# merkur-23m10.net
KiCad netlist of a schematic drawn in EAGLE
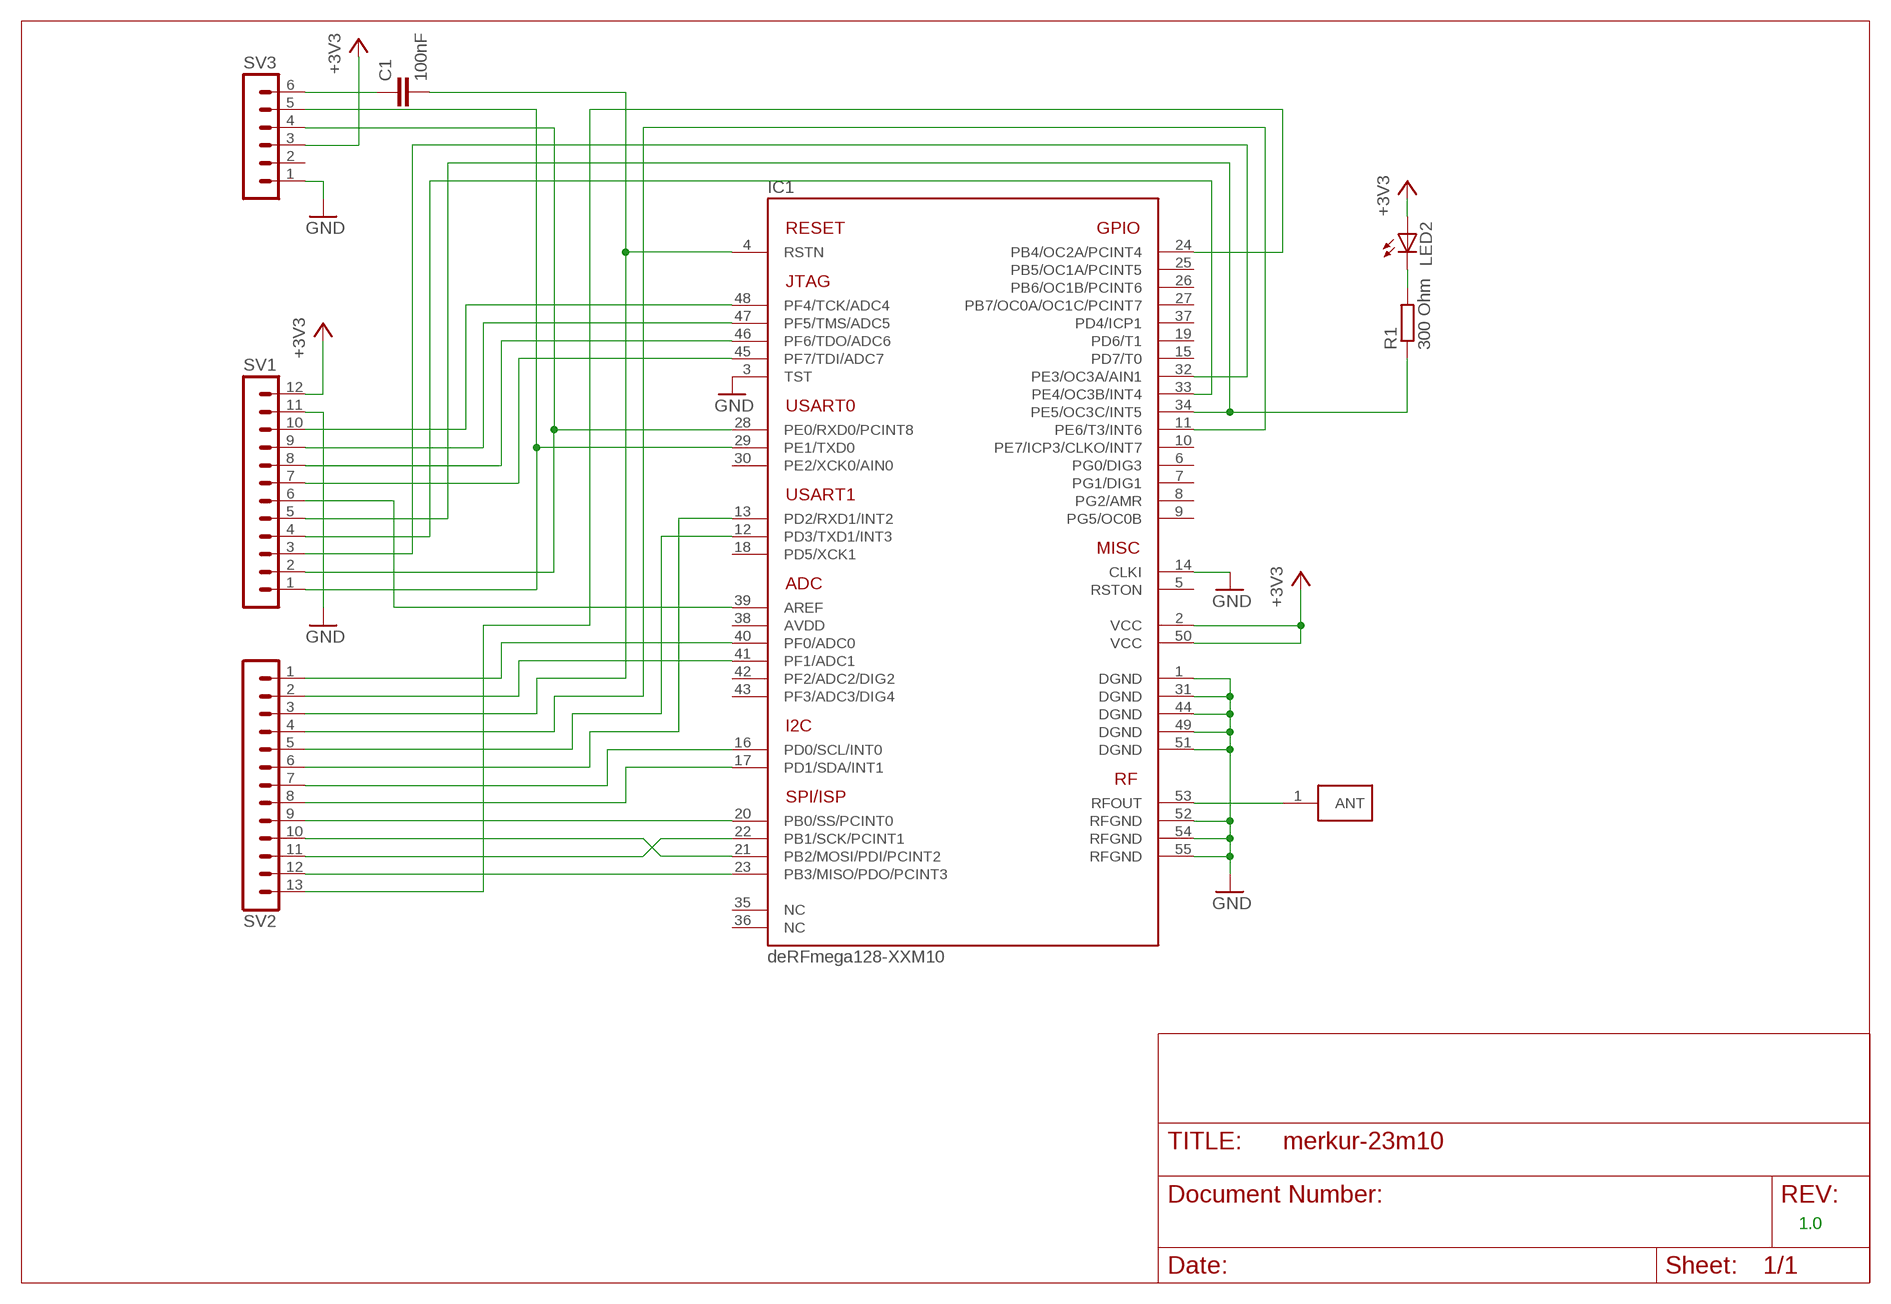
[diagram p0: schematic, sheet 1]

(export (version "E")
  (design (tool "Eeschema 10.0.6"))
  (components
    (comp (ref "C1")
      (value "100nF")
      (footprint "eagle-import:C0603")
      (libsource (lib "eagle-import") (part "C-EUC0603"))
    )
    (comp (ref "IC1")
      (value "DERFMEGA128-XXM10")
      (footprint "eagle-import:A-M10")
      (libsource (lib "eagle-import") (part "DERFMEGA128-XXM10"))
    )
    (comp (ref "LED2")
      (value "LEDCHIP-LED0603")
      (footprint "eagle-import:CHIP-LED0603")
      (libsource (lib "eagle-import") (part "LEDCHIP-LED0603"))
    )
    (comp (ref "R1")
      (value "300 Ohm")
      (footprint "eagle-import:R0603")
      (libsource (lib "eagle-import") (part "R-EU_R0603"))
    )
    (comp (ref "SV1")
      (value "MA12-1")
      (footprint "eagle-import:MA12-1")
      (libsource (lib "eagle-import") (part "MA12-1"))
    )
    (comp (ref "SV2")
      (value "MA13-1")
      (footprint "eagle-import:MA13-1")
      (libsource (lib "eagle-import") (part "MA13-1"))
    )
    (comp (ref "SV3")
      (value "MA06-1")
      (footprint "eagle-import:MA06-1")
      (libsource (lib "eagle-import") (part "MA06-1"))
    )
    (comp (ref "U$1")
      (value "PAD")
      (footprint "eagle-import:FE05-1")
      (libsource (lib "eagle-import") (part "PAD"))
    )
  )
  (nets
    (net (code "1") (name "+3V3") (class "Default")
      (node (ref "IC1") (pin "2") (pinfunction "VCC_2") (pintype "power_in"))
      (node (ref "IC1") (pin "50") (pinfunction "VCC_50") (pintype "power_in"))
      (node (ref "LED2") (pin "A") (pinfunction "A_A") (pintype "passive"))
      (node (ref "SV1") (pin "12") (pinfunction "12_12") (pintype "passive"))
      (node (ref "SV3") (pin "3") (pinfunction "3_3") (pintype "passive"))
    )
    (net (code "2") (name "/AVDD") (class "Default")
      (node (ref "IC1") (pin "38") (pinfunction "AVDD_38") (pintype "power_in"))
    )
    (net (code "3") (name "GND") (class "Default")
      (node (ref "IC1") (pin "1") (pinfunction "DGND_1") (pintype "power_in"))
      (node (ref "IC1") (pin "14") (pinfunction "CLKI_14") (pintype "input"))
      (node (ref "IC1") (pin "3") (pinfunction "TST_3") (pintype "bidirectional"))
      (node (ref "IC1") (pin "31") (pinfunction "DGND_31") (pintype "power_in"))
      (node (ref "IC1") (pin "44") (pinfunction "DGND_44") (pintype "power_in"))
      (node (ref "IC1") (pin "49") (pinfunction "DGND_49") (pintype "power_in"))
      (node (ref "IC1") (pin "51") (pinfunction "DGND_51") (pintype "power_in"))
      (node (ref "IC1") (pin "52") (pinfunction "RFGND_52") (pintype "power_in"))
      (node (ref "IC1") (pin "54") (pinfunction "RFGND_54") (pintype "power_in"))
      (node (ref "IC1") (pin "55") (pinfunction "RFGND_55") (pintype "power_in"))
      (node (ref "SV1") (pin "11") (pinfunction "11_11") (pintype "passive"))
      (node (ref "SV3") (pin "1") (pinfunction "1_1") (pintype "passive"))
    )
    (net (code "4") (name "Net-(C1-Pad1)") (class "Default")
      (node (ref "C1") (pin "1") (pinfunction "1_1") (pintype "passive"))
      (node (ref "SV3") (pin "6") (pinfunction "6_6") (pintype "passive"))
    )
    (net (code "5") (name "Net-(IC1-AREF)") (class "Default")
      (node (ref "IC1") (pin "39") (pinfunction "AREF_39") (pintype "bidirectional"))
      (node (ref "SV1") (pin "6") (pinfunction "6_6") (pintype "passive"))
    )
    (net (code "6") (name "Net-(IC1-PB0{slash}SS{slash}PCINT0)") (class "Default")
      (node (ref "IC1") (pin "20") (pinfunction "PB0/SS/PCINT0_20") (pintype "bidirectional"))
      (node (ref "SV2") (pin "9") (pinfunction "9_9") (pintype "passive"))
    )
    (net (code "7") (name "Net-(IC1-PB1{slash}SCK{slash}PCINT1)") (class "Default")
      (node (ref "IC1") (pin "22") (pinfunction "PB1/SCK/PCINT1_22") (pintype "bidirectional"))
      (node (ref "SV2") (pin "11") (pinfunction "11_11") (pintype "passive"))
    )
    (net (code "8") (name "Net-(IC1-PB2{slash}MOSI{slash}PDI{slash}PCINT2)") (class "Default")
      (node (ref "IC1") (pin "21") (pinfunction "PB2/MOSI/PDI/PCINT2_21") (pintype "bidirectional"))
      (node (ref "SV2") (pin "10") (pinfunction "10_10") (pintype "passive"))
    )
    (net (code "9") (name "Net-(IC1-PB3{slash}MISO{slash}PDO{slash}PCINT3)") (class "Default")
      (node (ref "IC1") (pin "23") (pinfunction "PB3/MISO/PDO/PCINT3_23") (pintype "bidirectional"))
      (node (ref "SV2") (pin "12") (pinfunction "12_12") (pintype "passive"))
    )
    (net (code "10") (name "Net-(IC1-PB4{slash}OC2A{slash}PCINT4)") (class "Default")
      (node (ref "IC1") (pin "24") (pinfunction "PB4/OC2A/PCINT4_24") (pintype "bidirectional"))
      (node (ref "SV2") (pin "13") (pinfunction "13_13") (pintype "passive"))
    )
    (net (code "11") (name "Net-(IC1-PD0{slash}SCL{slash}INT0)") (class "Default")
      (node (ref "IC1") (pin "16") (pinfunction "PD0/SCL/INT0_16") (pintype "bidirectional"))
      (node (ref "SV2") (pin "7") (pinfunction "7_7") (pintype "passive"))
    )
    (net (code "12") (name "Net-(IC1-PD1{slash}SDA{slash}INT1)") (class "Default")
      (node (ref "IC1") (pin "17") (pinfunction "PD1/SDA/INT1_17") (pintype "bidirectional"))
      (node (ref "SV2") (pin "8") (pinfunction "8_8") (pintype "passive"))
    )
    (net (code "13") (name "Net-(IC1-PD2{slash}RXD1{slash}INT2)") (class "Default")
      (node (ref "IC1") (pin "13") (pinfunction "PD2/RXD1/INT2_13") (pintype "bidirectional"))
      (node (ref "SV2") (pin "6") (pinfunction "6_6") (pintype "passive"))
    )
    (net (code "14") (name "Net-(IC1-PD3{slash}TXD1{slash}INT3)") (class "Default")
      (node (ref "IC1") (pin "12") (pinfunction "PD3/TXD1/INT3_12") (pintype "bidirectional"))
      (node (ref "SV2") (pin "5") (pinfunction "5_5") (pintype "passive"))
    )
    (net (code "15") (name "Net-(IC1-PE0{slash}RXD0{slash}PCINT8)") (class "Default")
      (node (ref "IC1") (pin "28") (pinfunction "PE0/RXD0/PCINT8_28") (pintype "bidirectional"))
      (node (ref "SV1") (pin "2") (pinfunction "2_2") (pintype "passive"))
      (node (ref "SV3") (pin "4") (pinfunction "4_4") (pintype "passive"))
    )
    (net (code "16") (name "Net-(IC1-PE1{slash}TXD0)") (class "Default")
      (node (ref "IC1") (pin "29") (pinfunction "PE1/TXD0_29") (pintype "bidirectional"))
      (node (ref "SV1") (pin "1") (pinfunction "1_1") (pintype "passive"))
      (node (ref "SV3") (pin "5") (pinfunction "5_5") (pintype "passive"))
    )
    (net (code "17") (name "Net-(IC1-PE3{slash}OC3A{slash}AIN1)") (class "Default")
      (node (ref "IC1") (pin "32") (pinfunction "PE3/OC3A/AIN1_32") (pintype "bidirectional"))
      (node (ref "SV1") (pin "3") (pinfunction "3_3") (pintype "passive"))
    )
    (net (code "18") (name "Net-(IC1-PE4{slash}OC3B{slash}INT4)") (class "Default")
      (node (ref "IC1") (pin "33") (pinfunction "PE4/OC3B/INT4_33") (pintype "bidirectional"))
      (node (ref "SV1") (pin "4") (pinfunction "4_4") (pintype "passive"))
    )
    (net (code "19") (name "Net-(IC1-PE5{slash}OC3C{slash}INT5)") (class "Default")
      (node (ref "IC1") (pin "34") (pinfunction "PE5/OC3C/INT5_34") (pintype "bidirectional"))
      (node (ref "R1") (pin "1") (pinfunction "1_1") (pintype "passive"))
      (node (ref "SV1") (pin "5") (pinfunction "5_5") (pintype "passive"))
    )
    (net (code "20") (name "Net-(IC1-PE6{slash}T3{slash}INT6)") (class "Default")
      (node (ref "IC1") (pin "11") (pinfunction "PE6/T3/INT6_11") (pintype "bidirectional"))
      (node (ref "SV2") (pin "4") (pinfunction "4_4") (pintype "passive"))
    )
    (net (code "21") (name "Net-(IC1-PF0{slash}ADC0)") (class "Default")
      (node (ref "IC1") (pin "40") (pinfunction "PF0/ADC0_40") (pintype "bidirectional"))
      (node (ref "SV2") (pin "1") (pinfunction "1_1") (pintype "passive"))
    )
    (net (code "22") (name "Net-(IC1-PF1{slash}ADC1)") (class "Default")
      (node (ref "IC1") (pin "41") (pinfunction "PF1/ADC1_41") (pintype "bidirectional"))
      (node (ref "SV2") (pin "2") (pinfunction "2_2") (pintype "passive"))
    )
    (net (code "23") (name "Net-(IC1-PF4{slash}TCK{slash}ADC4)") (class "Default")
      (node (ref "IC1") (pin "48") (pinfunction "PF4/TCK/ADC4_48") (pintype "bidirectional"))
      (node (ref "SV1") (pin "10") (pinfunction "10_10") (pintype "passive"))
    )
    (net (code "24") (name "Net-(IC1-PF5{slash}TMS{slash}ADC5)") (class "Default")
      (node (ref "IC1") (pin "47") (pinfunction "PF5/TMS/ADC5_47") (pintype "bidirectional"))
      (node (ref "SV1") (pin "9") (pinfunction "9_9") (pintype "passive"))
    )
    (net (code "25") (name "Net-(IC1-PF6{slash}TDO{slash}ADC6)") (class "Default")
      (node (ref "IC1") (pin "46") (pinfunction "PF6/TDO/ADC6_46") (pintype "bidirectional"))
      (node (ref "SV1") (pin "8") (pinfunction "8_8") (pintype "passive"))
    )
    (net (code "26") (name "Net-(IC1-PF7{slash}TDI{slash}ADC7)") (class "Default")
      (node (ref "IC1") (pin "45") (pinfunction "PF7/TDI/ADC7_45") (pintype "bidirectional"))
      (node (ref "SV1") (pin "7") (pinfunction "7_7") (pintype "passive"))
    )
    (net (code "27") (name "Net-(IC1-RFOUT)") (class "Default")
      (node (ref "IC1") (pin "53") (pinfunction "RFOUT_53") (pintype "power_in"))
      (node (ref "U$1") (pin "1") (pinfunction "ANT_1") (pintype "output"))
    )
    (net (code "28") (name "Net-(IC1-RSTN)") (class "Default")
      (node (ref "C1") (pin "2") (pinfunction "2_2") (pintype "passive"))
      (node (ref "IC1") (pin "4") (pinfunction "RSTN_4") (pintype "input"))
      (node (ref "SV2") (pin "3") (pinfunction "3_3") (pintype "passive"))
    )
    (net (code "29") (name "Net-(LED2-PadC)") (class "Default")
      (node (ref "LED2") (pin "C") (pinfunction "C_C") (pintype "passive"))
      (node (ref "R1") (pin "2") (pinfunction "2_2") (pintype "passive"))
    )
    (net (code "30") (name "unconnected-(IC1-NC-Pad35)") (class "Default")
      (node (ref "IC1") (pin "35") (pinfunction "NC_35") (pintype "no_connect"))
    )
    (net (code "31") (name "unconnected-(IC1-NC-Pad36)") (class "Default")
      (node (ref "IC1") (pin "36") (pinfunction "NC_36") (pintype "no_connect"))
    )
    (net (code "32") (name "unconnected-(IC1-PB5{slash}OC1A{slash}PCINT5-Pad25)") (class "Default")
      (node (ref "IC1") (pin "25") (pinfunction "PB5/OC1A/PCINT5_25") (pintype "bidirectional"))
    )
    (net (code "33") (name "unconnected-(IC1-PB6{slash}OC1B{slash}PCINT6-Pad26)") (class "Default")
      (node (ref "IC1") (pin "26") (pinfunction "PB6/OC1B/PCINT6_26") (pintype "bidirectional"))
    )
    (net (code "34") (name "unconnected-(IC1-PB7{slash}OC0A{slash}OC1C{slash}PCINT7-Pad27)") (class "Default")
      (node (ref "IC1") (pin "27") (pinfunction "PB7/OC0A/OC1C/PCINT7_27") (pintype "bidirectional"))
    )
    (net (code "35") (name "unconnected-(IC1-PD4{slash}ICP1-Pad37)") (class "Default")
      (node (ref "IC1") (pin "37") (pinfunction "PD4/ICP1_37") (pintype "bidirectional"))
    )
    (net (code "36") (name "unconnected-(IC1-PD5{slash}XCK1-Pad18)") (class "Default")
      (node (ref "IC1") (pin "18") (pinfunction "PD5/XCK1_18") (pintype "bidirectional"))
    )
    (net (code "37") (name "unconnected-(IC1-PD6{slash}T1-Pad19)") (class "Default")
      (node (ref "IC1") (pin "19") (pinfunction "PD6/T1_19") (pintype "bidirectional"))
    )
    (net (code "38") (name "unconnected-(IC1-PD7{slash}T0-Pad15)") (class "Default")
      (node (ref "IC1") (pin "15") (pinfunction "PD7/T0_15") (pintype "bidirectional"))
    )
    (net (code "39") (name "unconnected-(IC1-PE2{slash}XCK0{slash}AIN0-Pad30)") (class "Default")
      (node (ref "IC1") (pin "30") (pinfunction "PE2/XCK0/AIN0_30") (pintype "bidirectional"))
    )
    (net (code "40") (name "unconnected-(IC1-PE7{slash}ICP3{slash}CLKO{slash}INT7-Pad10)") (class "Default")
      (node (ref "IC1") (pin "10") (pinfunction "PE7/ICP3/CLKO/INT7_10") (pintype "bidirectional"))
    )
    (net (code "41") (name "unconnected-(IC1-PF2{slash}ADC2{slash}DIG2-Pad42)") (class "Default")
      (node (ref "IC1") (pin "42") (pinfunction "PF2/ADC2/DIG2_42") (pintype "bidirectional"))
    )
    (net (code "42") (name "unconnected-(IC1-PF3{slash}ADC3{slash}DIG4-Pad43)") (class "Default")
      (node (ref "IC1") (pin "43") (pinfunction "PF3/ADC3/DIG4_43") (pintype "bidirectional"))
    )
    (net (code "43") (name "unconnected-(IC1-PG0{slash}DIG3-Pad6)") (class "Default")
      (node (ref "IC1") (pin "6") (pinfunction "PG0/DIG3_6") (pintype "bidirectional"))
    )
    (net (code "44") (name "unconnected-(IC1-PG1{slash}DIG1-Pad7)") (class "Default")
      (node (ref "IC1") (pin "7") (pinfunction "PG1/DIG1_7") (pintype "bidirectional"))
    )
    (net (code "45") (name "unconnected-(IC1-PG2{slash}AMR-Pad8)") (class "Default")
      (node (ref "IC1") (pin "8") (pinfunction "PG2/AMR_8") (pintype "bidirectional"))
    )
    (net (code "46") (name "unconnected-(IC1-PG5{slash}OC0B-Pad9)") (class "Default")
      (node (ref "IC1") (pin "9") (pinfunction "PG5/OC0B_9") (pintype "bidirectional"))
    )
    (net (code "47") (name "unconnected-(IC1-RSTON-Pad5)") (class "Default")
      (node (ref "IC1") (pin "5") (pinfunction "RSTON_5") (pintype "output"))
    )
    (net (code "48") (name "unconnected-(SV3-Pad2)") (class "Default")
      (node (ref "SV3") (pin "2") (pinfunction "2_2") (pintype "passive"))
    )
  )
)
